# power.net
KiCad netlist of a schematic drawn in Altium Designer
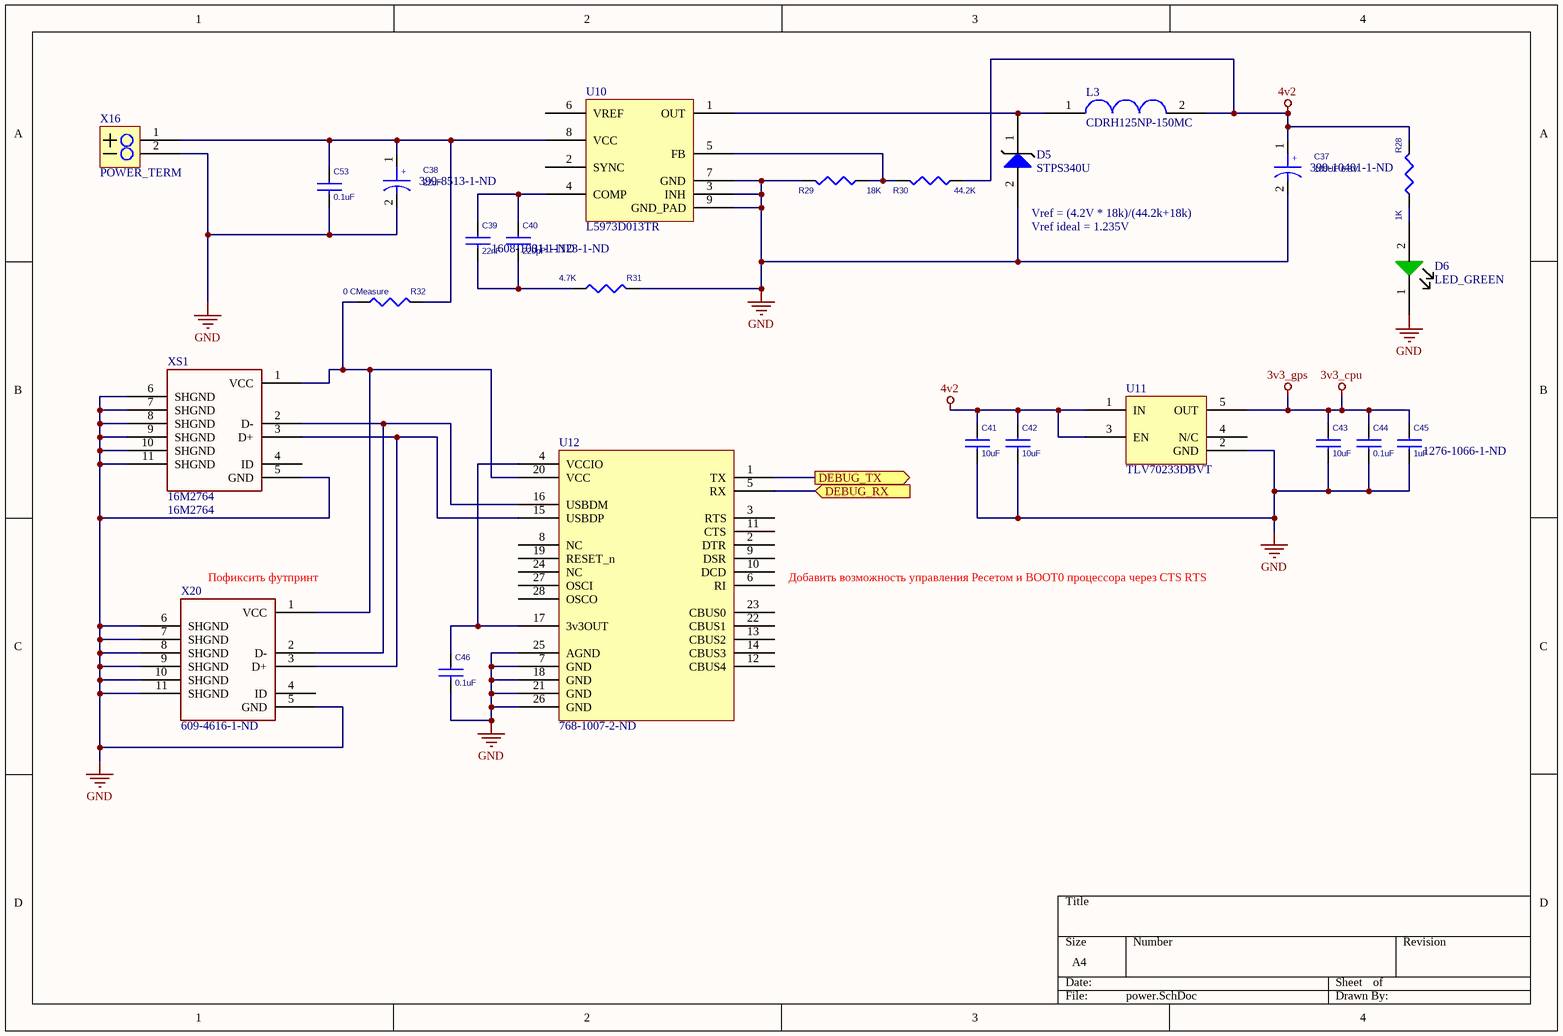
[diagram p0: power.SchDoc]

(export (version "E")
  (design (tool "Eeschema 10.0.6"))
  (components
    (comp (ref "C37")
      (value "100UF 6.3V")
      (footprint "CAPMP6133X31N")
      (description "CAP 100uF; 6.3V; Case: C; ESR:150mOhm")
      (fields (field (name "SUPPLIER PART NUMBER 1") "399-10401-1-ND"))
      (libsource (lib "Capacitors") (part "CAP_SMD_100UF_10%"))
    )
    (comp (ref "C38")
      (value "22uF")
      (footprint "CAPMP7143X31N")
      (description "CAP SMD 35volts 22uF 10% ESR=300mOhms")
      (fields (field (name "SUPPLIER PART NUMBER 1") "399-8513-1-ND"))
      (libsource (lib "Capacitors") (part "CAP_SMD_22UF_10%"))
    )
    (comp (ref "C39")
      (value "22nF")
      (footprint "CAPC2012X09M")
      (description "CAP 22NF 50V 10% X7R 0805")
      (fields (field (name "SUPPLIER PART NUMBER 1") "1608-1001-1-ND"))
      (libsource (lib "Capacitors") (part "CAP_SMD_22nF_10%"))
    )
    (comp (ref "C40")
      (value "220pF")
      (footprint "CAPC2012X09M")
      (description "CAP 220PF 50V 10%  0805")
      (fields (field (name "SUPPLIER PART NUMBER 1") "311-1123-1-ND"))
      (libsource (lib "Capacitors") (part "CAP_SMD_220pF_10%"))
    )
    (comp (ref "C41")
      (value "10uF")
      (footprint "CAPC2012X09M")
      (description "CAP CER 10UF 16V 20% X5R 0805")
      (libsource (lib "Capacitors") (part "CAP_SMD_10UF_20%"))
    )
    (comp (ref "C42")
      (value "10uF")
      (footprint "CAPC2012X09M")
      (description "CAP CER 10UF 16V 20% X5R 0805")
      (libsource (lib "Capacitors") (part "CAP_SMD_10UF_20%"))
    )
    (comp (ref "C43")
      (value "10uF")
      (footprint "CAPC2012X09M")
      (description "CAP CER 10UF 16V 20% X5R 0805")
      (libsource (lib "Capacitors") (part "CAP_SMD_10UF_20%"))
    )
    (comp (ref "C44")
      (value "0.1uF")
      (footprint "CAPC2012X09M")
      (description "CAP CER 0.1UF 25V 10% X7R 0805")
      (libsource (lib "Capacitors") (part "CAP_SMD_0.1UF_10%"))
    )
    (comp (ref "C45")
      (value "1uF")
      (footprint "CAPC2012X09M")
      (description "MLCC; 1uF; 25V; X7R; ±10%; SMD; 0805;")
      (fields (field (name "SUPPLIER PART NUMBER 1") "1276-1066-1-ND"))
      (libsource (lib "Capacitors") (part "CAP_SMD_1uF_10%"))
    )
    (comp (ref "C46")
      (value "0.1uF")
      (footprint "CAPC2012X09M")
      (description "CAP CER 0.1UF 25V 10% X7R 0805")
      (libsource (lib "Capacitors") (part "CAP_SMD_0.1UF_10%"))
    )
    (comp (ref "C53")
      (value "0.1uF")
      (footprint "CAPC2012X09M")
      (description "CAP CER 0.1UF 25V 10% X7R 0805")
      (libsource (lib "Capacitors") (part "CAP_SMD_0.1UF_10%"))
    )
    (comp (ref "D5")
      (value "STPS340U")
      (footprint "SODFL535X265-2N")
      (description "DIODE, ZENER, 20V, 3W")
      (libsource (lib "Passive") (part "STPS340U"))
    )
    (comp (ref "D6")
      (value "LED_GREEN")
      (footprint "DIOC2012X11N")
      (libsource (lib "Passive") (part "LED_GREEN"))
    )
    (comp (ref "L3")
      (value "CDRH125NP-150MC")
      (footprint "INDP123123X40N_SUMIDA")
      (libsource (lib "Passive") (part "IND_15uH_3.3A"))
    )
    (comp (ref "R28")
      (value "1K")
      (footprint "RESC2013X06M")
      (description "RES - 1K OHM, 5%, 1/8W, 0805 SMD")
      (libsource (lib "Resistors") (part "RES_SMD_1K_5%"))
    )
    (comp (ref "R29")
      (value "18K")
      (footprint "RESC2013X06M")
      (description "RES 18K OHM 1/8W 1% 0805 SMD")
      (libsource (lib "Resistors") (part "RES_SMD_18K_1%"))
    )
    (comp (ref "R30")
      (value "44.2K")
      (footprint "RESC2013X06M")
      (description "RES 45.3K OHM 1/8W 1% 0805 SMD")
      (libsource (lib "Resistors") (part "RES_SMD_45.3K"))
    )
    (comp (ref "R31")
      (value "4.7K")
      (footprint "RESC2013X06M")
      (description "RES 4.7K OHM 1/8W 1% 0805 SMD")
      (libsource (lib "Resistors") (part "RES_SMD_4.7K_1%"))
    )
    (comp (ref "R32")
      (value "0 CMeasure")
      (footprint "RESC2013X06M_CMEASURE")
      (description "RES 0.0 OHM 1/8W JUMP 0805 SMD")
      (libsource (lib "Resistors") (part "RES_SMD_0_CURRENT"))
    )
    (comp (ref "U10")
      (value "L5973D013TR")
      (footprint "SOIC127P600X175_HS-9N")
      (description "IC REG BUCK ADJ 2.5A SOIC8")
      (libsource (lib "TruthEar") (part "L5973D013TR"))
    )
    (comp (ref "U11")
      (value "TLV70233DBVT")
      (footprint "SOT95P280X145-5M")
      (libsource (lib "TruthEar") (part "TLV70233DBVT"))
    )
    (comp (ref "U12")
      (value "FT232RL")
      (footprint "SOP65P780X200-28M")
      (fields (field (name "SUPPLIER PART NUMBER 1") "768-1007-2-ND"))
      (libsource (lib "TruthEar") (part "FT232RL"))
    )
    (comp (ref "X16")
      (value "POWER_TERM")
      (footprint "PH5")
      (libsource (lib "Connectors") (part "POWER_TERM"))
    )
    (comp (ref "X20")
      (value "10118193-0001LF")
      (footprint "USB_MICRO_10118193")
      (fields (field (name "SUPPLIER PART NUMBER 1") "609-4616-1-ND"))
      (libsource (lib "Connectors") (part "USB_MICRO"))
    )
    (comp (ref "XS1")
      (value "16M2764")
      (footprint "USB_MINI_16M2764")
      (fields (field (name "SUPPLIER PART NUMBER 1") "16M2764"))
      (libsource (lib "Connectors") (part "USB_MINI_16M2764"))
    )
  )
  (nets
    (net (code "1") (name "/DEBUG_RX") (class "Default")
      (node (ref "U12") (pin "5") (pinfunction "RX_5") (pintype "power_in"))
    )
    (net (code "2") (name "/DEBUG_TX") (class "Default")
      (node (ref "U12") (pin "1") (pinfunction "TX_1") (pintype "power_in"))
    )
    (net (code "3") (name "3v3_cpu") (class "Default")
      (node (ref "C43") (pin "1") (pinfunction "1_1") (pintype "passive"))
      (node (ref "C44") (pin "1") (pinfunction "1_1") (pintype "passive"))
      (node (ref "C45") (pin "1") (pinfunction "1_1") (pintype "passive"))
      (node (ref "U11") (pin "5") (pinfunction "OUT_5") (pintype "passive"))
    )
    (net (code "4") (name "4v2") (class "Default")
      (node (ref "C37") (pin "1") (pinfunction "1_1") (pintype "passive"))
      (node (ref "C41") (pin "1") (pinfunction "1_1") (pintype "passive"))
      (node (ref "C42") (pin "1") (pinfunction "1_1") (pintype "passive"))
      (node (ref "L3") (pin "2") (pinfunction "2_2") (pintype "passive"))
      (node (ref "R28") (pin "2") (pinfunction "2_2") (pintype "passive"))
      (node (ref "R30") (pin "1") (pinfunction "1_1") (pintype "passive"))
      (node (ref "U11") (pin "1") (pinfunction "IN_1") (pintype "passive"))
      (node (ref "U11") (pin "3") (pinfunction "EN_3") (pintype "passive"))
    )
    (net (code "5") (name "GND") (class "Default")
      (node (ref "C37") (pin "2") (pinfunction "2_2") (pintype "passive"))
      (node (ref "C38") (pin "2") (pinfunction "2_2") (pintype "passive"))
      (node (ref "C41") (pin "2") (pinfunction "2_2") (pintype "passive"))
      (node (ref "C42") (pin "2") (pinfunction "2_2") (pintype "passive"))
      (node (ref "C43") (pin "2") (pinfunction "2_2") (pintype "passive"))
      (node (ref "C44") (pin "2") (pinfunction "2_2") (pintype "passive"))
      (node (ref "C45") (pin "2") (pinfunction "2_2") (pintype "passive"))
      (node (ref "C46") (pin "2") (pinfunction "2_2") (pintype "passive"))
      (node (ref "C53") (pin "2") (pinfunction "2_2") (pintype "passive"))
      (node (ref "D5") (pin "2") (pinfunction "A_2") (pintype "passive"))
      (node (ref "D6") (pin "1") (pinfunction "C_1") (pintype "passive"))
      (node (ref "R29") (pin "2") (pinfunction "2_2") (pintype "passive"))
      (node (ref "R31") (pin "2") (pinfunction "2_2") (pintype "passive"))
      (node (ref "U10") (pin "3") (pinfunction "INH_3") (pintype "passive"))
      (node (ref "U10") (pin "7") (pinfunction "GND_7") (pintype "passive"))
      (node (ref "U10") (pin "9") (pinfunction "GND_PAD_9") (pintype "passive"))
      (node (ref "U11") (pin "2") (pinfunction "GND_2") (pintype "passive"))
      (node (ref "U12") (pin "18") (pinfunction "GND_18") (pintype "power_in"))
      (node (ref "U12") (pin "21") (pinfunction "GND_21") (pintype "power_in"))
      (node (ref "U12") (pin "25") (pinfunction "AGND_25") (pintype "power_in"))
      (node (ref "U12") (pin "26") (pinfunction "GND_26") (pintype "power_in"))
      (node (ref "U12") (pin "7") (pinfunction "GND_7") (pintype "power_in"))
      (node (ref "X16") (pin "2") (pinfunction "2_2") (pintype "passive"))
      (node (ref "X20") (pin "10") (pinfunction "SHGND_10") (pintype "passive"))
      (node (ref "X20") (pin "11") (pinfunction "SHGND_11") (pintype "passive"))
      (node (ref "X20") (pin "5") (pinfunction "GND_5") (pintype "passive"))
      (node (ref "X20") (pin "6") (pinfunction "SHGND_6") (pintype "passive"))
      (node (ref "X20") (pin "7") (pinfunction "SHGND_7") (pintype "passive"))
      (node (ref "X20") (pin "8") (pinfunction "SHGND_8") (pintype "passive"))
      (node (ref "X20") (pin "9") (pinfunction "SHGND_9") (pintype "passive"))
      (node (ref "XS1") (pin "10") (pinfunction "SHGND_10") (pintype "passive"))
      (node (ref "XS1") (pin "11") (pinfunction "SHGND_11") (pintype "passive"))
      (node (ref "XS1") (pin "5") (pinfunction "GND_5") (pintype "passive"))
      (node (ref "XS1") (pin "6") (pinfunction "SHGND_6") (pintype "passive"))
      (node (ref "XS1") (pin "7") (pinfunction "SHGND_7") (pintype "passive"))
      (node (ref "XS1") (pin "8") (pinfunction "SHGND_8") (pintype "passive"))
      (node (ref "XS1") (pin "9") (pinfunction "SHGND_9") (pintype "passive"))
    )
    (net (code "6") (name "Net-(C39-Pad2)") (class "Default")
      (node (ref "C39") (pin "2") (pinfunction "2_2") (pintype "passive"))
      (node (ref "C40") (pin "2") (pinfunction "2_2") (pintype "passive"))
      (node (ref "R31") (pin "1") (pinfunction "1_1") (pintype "passive"))
    )
    (net (code "7") (name "Net-(D5-C)") (class "Default")
      (node (ref "D5") (pin "1") (pinfunction "C_1") (pintype "passive"))
      (node (ref "L3") (pin "1") (pinfunction "1_1") (pintype "passive"))
      (node (ref "U10") (pin "1") (pinfunction "OUT_1") (pintype "passive"))
    )
    (net (code "8") (name "Net-(D6-A)") (class "Default")
      (node (ref "D6") (pin "2") (pinfunction "A_2") (pintype "passive"))
      (node (ref "R28") (pin "1") (pinfunction "1_1") (pintype "passive"))
    )
    (net (code "9") (name "Net-(U10-COMP)") (class "Default")
      (node (ref "C39") (pin "1") (pinfunction "1_1") (pintype "passive"))
      (node (ref "C40") (pin "1") (pinfunction "1_1") (pintype "passive"))
      (node (ref "U10") (pin "4") (pinfunction "COMP_4") (pintype "passive"))
    )
    (net (code "10") (name "Net-(U10-FB)") (class "Default")
      (node (ref "R29") (pin "1") (pinfunction "1_1") (pintype "passive"))
      (node (ref "R30") (pin "2") (pinfunction "2_2") (pintype "passive"))
      (node (ref "U10") (pin "5") (pinfunction "FB_5") (pintype "passive"))
    )
    (net (code "11") (name "Net-(U10-VCC)") (class "Default")
      (node (ref "C38") (pin "1") (pinfunction "1_1") (pintype "passive"))
      (node (ref "C53") (pin "1") (pinfunction "1_1") (pintype "passive"))
      (node (ref "R32") (pin "2") (pinfunction "2_2") (pintype "passive"))
      (node (ref "U10") (pin "8") (pinfunction "VCC_8") (pintype "passive"))
      (node (ref "X16") (pin "1") (pinfunction "1_1") (pintype "passive"))
    )
    (net (code "12") (name "Net-(U12-3v3OUT)") (class "Default")
      (node (ref "C46") (pin "1") (pinfunction "1_1") (pintype "passive"))
      (node (ref "U12") (pin "17") (pinfunction "3v3OUT_17") (pintype "power_in"))
      (node (ref "U12") (pin "4") (pinfunction "VCCIO_4") (pintype "power_in"))
    )
    (net (code "13") (name "Net-(U12-USBDM)") (class "Default")
      (node (ref "U12") (pin "16") (pinfunction "USBDM_16") (pintype "power_in"))
      (node (ref "X20") (pin "2") (pinfunction "D-_2") (pintype "passive"))
      (node (ref "XS1") (pin "2") (pinfunction "D-_2") (pintype "passive"))
    )
    (net (code "14") (name "Net-(U12-USBDP)") (class "Default")
      (node (ref "U12") (pin "15") (pinfunction "USBDP_15") (pintype "power_in"))
      (node (ref "X20") (pin "3") (pinfunction "D+_3") (pintype "passive"))
      (node (ref "XS1") (pin "3") (pinfunction "D+_3") (pintype "passive"))
    )
    (net (code "15") (name "Net-(U12-VCC)") (class "Default")
      (node (ref "R32") (pin "1") (pinfunction "1_1") (pintype "passive"))
      (node (ref "U12") (pin "20") (pinfunction "VCC_20") (pintype "power_in"))
      (node (ref "X20") (pin "1") (pinfunction "VCC_1") (pintype "passive"))
      (node (ref "XS1") (pin "1") (pinfunction "VCC_1") (pintype "passive"))
    )
    (net (code "16") (name "unconnected-(U10-SYNC-Pad2)") (class "Default")
      (node (ref "U10") (pin "2") (pinfunction "SYNC_2") (pintype "passive"))
    )
    (net (code "17") (name "unconnected-(U10-VREF-Pad6)") (class "Default")
      (node (ref "U10") (pin "6") (pinfunction "VREF_6") (pintype "passive"))
    )
    (net (code "18") (name "unconnected-(U11-N{slash}C-Pad4)") (class "Default")
      (node (ref "U11") (pin "4") (pinfunction "N/C_4") (pintype "passive"))
    )
    (net (code "19") (name "unconnected-(U12-CBUS0-Pad23)") (class "Default")
      (node (ref "U12") (pin "23") (pinfunction "CBUS0_23") (pintype "power_in"))
    )
    (net (code "20") (name "unconnected-(U12-CBUS1-Pad22)") (class "Default")
      (node (ref "U12") (pin "22") (pinfunction "CBUS1_22") (pintype "power_in"))
    )
    (net (code "21") (name "unconnected-(U12-CBUS2-Pad13)") (class "Default")
      (node (ref "U12") (pin "13") (pinfunction "CBUS2_13") (pintype "power_in"))
    )
    (net (code "22") (name "unconnected-(U12-CBUS3-Pad14)") (class "Default")
      (node (ref "U12") (pin "14") (pinfunction "CBUS3_14") (pintype "power_in"))
    )
    (net (code "23") (name "unconnected-(U12-CBUS4-Pad12)") (class "Default")
      (node (ref "U12") (pin "12") (pinfunction "CBUS4_12") (pintype "power_in"))
    )
    (net (code "24") (name "unconnected-(U12-CTS-Pad11)") (class "Default")
      (node (ref "U12") (pin "11") (pinfunction "CTS_11") (pintype "power_in"))
    )
    (net (code "25") (name "unconnected-(U12-DCD-Pad10)") (class "Default")
      (node (ref "U12") (pin "10") (pinfunction "DCD_10") (pintype "power_in"))
    )
    (net (code "26") (name "unconnected-(U12-DSR-Pad9)") (class "Default")
      (node (ref "U12") (pin "9") (pinfunction "DSR_9") (pintype "power_in"))
    )
    (net (code "27") (name "unconnected-(U12-DTR-Pad2)") (class "Default")
      (node (ref "U12") (pin "2") (pinfunction "DTR_2") (pintype "power_in"))
    )
    (net (code "28") (name "unconnected-(U12-NC-Pad8)") (class "Default")
      (node (ref "U12") (pin "8") (pinfunction "NC_8") (pintype "power_in"))
    )
    (net (code "29") (name "unconnected-(U12-NC-Pad24)") (class "Default")
      (node (ref "U12") (pin "24") (pinfunction "NC_24") (pintype "power_in"))
    )
    (net (code "30") (name "unconnected-(U12-OSCI-Pad27)") (class "Default")
      (node (ref "U12") (pin "27") (pinfunction "OSCI_27") (pintype "power_in"))
    )
    (net (code "31") (name "unconnected-(U12-OSCO-Pad28)") (class "Default")
      (node (ref "U12") (pin "28") (pinfunction "OSCO_28") (pintype "power_in"))
    )
    (net (code "32") (name "unconnected-(U12-RESET_n-Pad19)") (class "Default")
      (node (ref "U12") (pin "19") (pinfunction "RESET_n_19") (pintype "power_in"))
    )
    (net (code "33") (name "unconnected-(U12-RI-Pad6)") (class "Default")
      (node (ref "U12") (pin "6") (pinfunction "RI_6") (pintype "power_in"))
    )
    (net (code "34") (name "unconnected-(U12-RTS-Pad3)") (class "Default")
      (node (ref "U12") (pin "3") (pinfunction "RTS_3") (pintype "power_in"))
    )
    (net (code "35") (name "unconnected-(X20-ID-Pad4)") (class "Default")
      (node (ref "X20") (pin "4") (pinfunction "ID_4") (pintype "passive"))
    )
    (net (code "36") (name "unconnected-(XS1-ID-Pad4)") (class "Default")
      (node (ref "XS1") (pin "4") (pinfunction "ID_4") (pintype "passive"))
    )
  )
)
